# rtu01n02.net
KiCad netlist of a schematic drawn in EAGLE
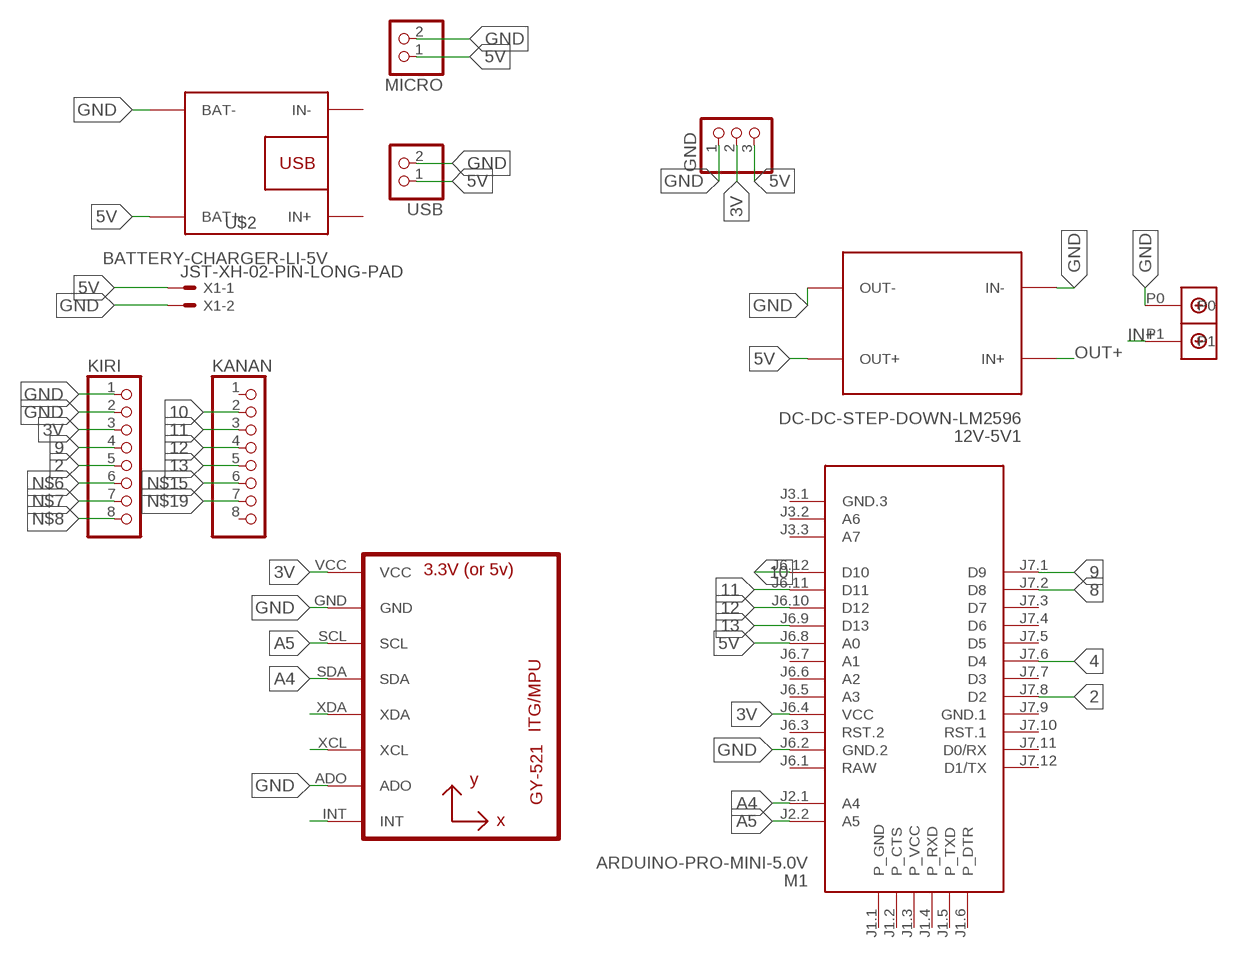
[diagram p0: schematic, sheet 1]

(export (version "E")
  (design (tool "Eeschema 10.0.6"))
  (components
    (comp (ref "12V-5V1")
      (value "DC-DC-STEP-DOWN-LM2596")
      (footprint "eagle-import:DC-DC-STEP-DOWN-LM2596")
      (libsource (lib "eagle-import") (part "DC-DC-STEP-DOWN-LM2596"))
    )
    (comp (ref "GND")
      (value "PINHD-1X3")
      (footprint "eagle-import:1X03")
      (libsource (lib "eagle-import") (part "PINHD-1X3"))
    )
    (comp (ref "KANAN")
      (value "PINHD-1X8")
      (footprint "eagle-import:1X08")
      (libsource (lib "eagle-import") (part "PINHD-1X8"))
    )
    (comp (ref "KIRI")
      (value "PINHD-1X8")
      (footprint "eagle-import:1X08")
      (libsource (lib "eagle-import") (part "PINHD-1X8"))
    )
    (comp (ref "M1")
      (value "ARDUINO-PRO-MINI-5.0V")
      (footprint "eagle-import:ARDUINO-PRO-MINI")
      (libsource (lib "eagle-import") (part "ARDUINO-PRO-MINI-5.0V"))
    )
    (comp (ref "MICRO")
      (value "PINHD-1X2")
      (footprint "eagle-import:1X02")
      (libsource (lib "eagle-import") (part "PINHD-1X2"))
    )
    (comp (ref "U$1")
      (value "DBCONN-1X2")
      (footprint "eagle-import:DBCONN-1X2")
      (libsource (lib "eagle-import") (part "DBCONN-1X2"))
    )
    (comp (ref "U$2")
      (value "BATTERY-CHARGER-LI-5V")
      (footprint "eagle-import:BATTERY-CHARGER-LI-5V")
      (libsource (lib "eagle-import") (part "BATTERY-CHARGER-LI-5V"))
    )
    (comp (ref "U1")
      (value "GY-521MPU6050")
      (footprint "eagle-import:GY-521")
      (libsource (lib "eagle-import") (part "GY-521MPU6050"))
    )
    (comp (ref "USB")
      (value "PINHD-1X2")
      (footprint "eagle-import:1X02")
      (libsource (lib "eagle-import") (part "PINHD-1X2"))
    )
    (comp (ref "X1")
      (value "JST-XH-02-PIN-LONG-PAD")
      (footprint "eagle-import:JST-XH-02-PACKAGE-LONG-PAD")
      (libsource (lib "eagle-import") (part "JST-XH-02-PIN-LONG-PAD"))
    )
  )
  (nets
    (net (code "1") (name "/GND.1") (class "Default")
      (node (ref "M1") (pin "J7.9") (pinfunction "GND.1_J7.9") (pintype "power_in"))
    )
    (net (code "2") (name "/IN+") (class "Default")
      (node (ref "U$1") (pin "P1") (pinfunction "P1_P1") (pintype "bidirectional"))
    )
    (net (code "3") (name "/OUT+") (class "Default")
      (node (ref "12V-5V1") (pin "IN+") (pinfunction "IN+_IN+") (pintype "bidirectional"))
    )
    (net (code "4") (name "/RAW") (class "Default")
      (node (ref "M1") (pin "J6.1") (pinfunction "RAW_J6.1") (pintype "power_in"))
    )
    (net (code "5") (name "2") (class "Default")
      (node (ref "KIRI") (pin "5") (pinfunction "5_5") (pintype "passive"))
      (node (ref "M1") (pin "J7.8") (pinfunction "D2_J7.8") (pintype "bidirectional"))
    )
    (net (code "6") (name "3V") (class "Default")
      (node (ref "GND") (pin "2") (pinfunction "2_2") (pintype "passive"))
      (node (ref "KIRI") (pin "3") (pinfunction "3_3") (pintype "passive"))
      (node (ref "M1") (pin "J6.4") (pinfunction "VCC_J6.4") (pintype "power_in"))
      (node (ref "U1") (pin "VCC") (pinfunction "VCC_VCC") (pintype "bidirectional"))
    )
    (net (code "7") (name "4") (class "Default")
      (node (ref "M1") (pin "J7.6") (pinfunction "D4_J7.6") (pintype "bidirectional"))
    )
    (net (code "8") (name "5V") (class "Default")
      (node (ref "12V-5V1") (pin "OUT+") (pinfunction "OUT+_OUT+") (pintype "bidirectional"))
      (node (ref "GND") (pin "3") (pinfunction "3_3") (pintype "passive"))
      (node (ref "M1") (pin "J6.8") (pinfunction "A0_J6.8") (pintype "bidirectional"))
      (node (ref "MICRO") (pin "1") (pinfunction "1_1") (pintype "passive"))
      (node (ref "U$2") (pin "BAT+") (pinfunction "BAT+_BAT+") (pintype "bidirectional"))
      (node (ref "USB") (pin "1") (pinfunction "1_1") (pintype "passive"))
      (node (ref "X1") (pin "1") (pinfunction "S_1") (pintype "passive"))
    )
    (net (code "9") (name "8") (class "Default")
      (node (ref "M1") (pin "J7.2") (pinfunction "D8_J7.2") (pintype "bidirectional"))
    )
    (net (code "10") (name "9") (class "Default")
      (node (ref "KIRI") (pin "4") (pinfunction "4_4") (pintype "passive"))
      (node (ref "M1") (pin "J7.1") (pinfunction "D9_J7.1") (pintype "bidirectional"))
    )
    (net (code "11") (name "10") (class "Default")
      (node (ref "KANAN") (pin "2") (pinfunction "2_2") (pintype "passive"))
      (node (ref "M1") (pin "J6.12") (pinfunction "D10_J6.12") (pintype "bidirectional"))
    )
    (net (code "12") (name "11") (class "Default")
      (node (ref "KANAN") (pin "3") (pinfunction "3_3") (pintype "passive"))
      (node (ref "M1") (pin "J6.11") (pinfunction "D11_J6.11") (pintype "bidirectional"))
    )
    (net (code "13") (name "12") (class "Default")
      (node (ref "KANAN") (pin "4") (pinfunction "4_4") (pintype "passive"))
      (node (ref "M1") (pin "J6.10") (pinfunction "D12_J6.10") (pintype "bidirectional"))
    )
    (net (code "14") (name "13") (class "Default")
      (node (ref "KANAN") (pin "5") (pinfunction "5_5") (pintype "passive"))
      (node (ref "M1") (pin "J6.9") (pinfunction "D13_J6.9") (pintype "bidirectional"))
    )
    (net (code "15") (name "A4") (class "Default")
      (node (ref "M1") (pin "J2.1") (pinfunction "A4_J2.1") (pintype "bidirectional"))
      (node (ref "U1") (pin "SDA") (pinfunction "SDA_SDA") (pintype "bidirectional"))
    )
    (net (code "16") (name "A5") (class "Default")
      (node (ref "M1") (pin "J2.2") (pinfunction "A5_J2.2") (pintype "bidirectional"))
      (node (ref "U1") (pin "SCL") (pinfunction "SCL_SCL") (pintype "bidirectional"))
    )
    (net (code "17") (name "GND") (class "Default")
      (node (ref "12V-5V1") (pin "IN-") (pinfunction "IN-_IN-") (pintype "bidirectional"))
      (node (ref "12V-5V1") (pin "OUT-") (pinfunction "OUT-_OUT-") (pintype "bidirectional"))
      (node (ref "GND") (pin "1") (pinfunction "1_1") (pintype "passive"))
      (node (ref "KIRI") (pin "1") (pinfunction "1_1") (pintype "passive"))
      (node (ref "KIRI") (pin "2") (pinfunction "2_2") (pintype "passive"))
      (node (ref "M1") (pin "J6.2") (pinfunction "GND.2_J6.2") (pintype "power_in"))
      (node (ref "MICRO") (pin "2") (pinfunction "2_2") (pintype "passive"))
      (node (ref "U$1") (pin "P0") (pinfunction "P0_P0") (pintype "bidirectional"))
      (node (ref "U$2") (pin "BAT-") (pinfunction "BAT-_BAT-") (pintype "bidirectional"))
      (node (ref "U1") (pin "ADO") (pinfunction "ADO_ADO") (pintype "bidirectional"))
      (node (ref "U1") (pin "GND") (pinfunction "GND_GND") (pintype "bidirectional"))
      (node (ref "USB") (pin "2") (pinfunction "2_2") (pintype "passive"))
      (node (ref "X1") (pin "2") (pinfunction "S_2") (pintype "passive"))
    )
    (net (code "18") (name "N$6") (class "Default")
      (node (ref "KIRI") (pin "6") (pinfunction "6_6") (pintype "passive"))
    )
    (net (code "19") (name "N$7") (class "Default")
      (node (ref "KIRI") (pin "7") (pinfunction "7_7") (pintype "passive"))
    )
    (net (code "20") (name "N$8") (class "Default")
      (node (ref "KIRI") (pin "8") (pinfunction "8_8") (pintype "passive"))
    )
    (net (code "21") (name "N$15") (class "Default")
      (node (ref "KANAN") (pin "6") (pinfunction "6_6") (pintype "passive"))
    )
    (net (code "22") (name "N$19") (class "Default")
      (node (ref "KANAN") (pin "7") (pinfunction "7_7") (pintype "passive"))
    )
    (net (code "23") (name "unconnected-(KANAN-Pad1)") (class "Default")
      (node (ref "KANAN") (pin "1") (pinfunction "1_1") (pintype "passive"))
    )
    (net (code "24") (name "unconnected-(KANAN-Pad8)") (class "Default")
      (node (ref "KANAN") (pin "8") (pinfunction "8_8") (pintype "passive"))
    )
    (net (code "25") (name "unconnected-(M1-A1-PadJ6.7)") (class "Default")
      (node (ref "M1") (pin "J6.7") (pinfunction "A1_J6.7") (pintype "bidirectional"))
    )
    (net (code "26") (name "unconnected-(M1-A2-PadJ6.6)") (class "Default")
      (node (ref "M1") (pin "J6.6") (pinfunction "A2_J6.6") (pintype "bidirectional"))
    )
    (net (code "27") (name "unconnected-(M1-A3-PadJ6.5)") (class "Default")
      (node (ref "M1") (pin "J6.5") (pinfunction "A3_J6.5") (pintype "bidirectional"))
    )
    (net (code "28") (name "unconnected-(M1-A6-PadJ3.2)") (class "Default")
      (node (ref "M1") (pin "J3.2") (pinfunction "A6_J3.2") (pintype "bidirectional"))
    )
    (net (code "29") (name "unconnected-(M1-A7-PadJ3.3)") (class "Default")
      (node (ref "M1") (pin "J3.3") (pinfunction "A7_J3.3") (pintype "bidirectional"))
    )
    (net (code "30") (name "unconnected-(M1-D0{slash}RX-PadJ7.11)") (class "Default")
      (node (ref "M1") (pin "J7.11") (pinfunction "D0/RX_J7.11") (pintype "bidirectional"))
    )
    (net (code "31") (name "unconnected-(M1-D1{slash}TX-PadJ7.12)") (class "Default")
      (node (ref "M1") (pin "J7.12") (pinfunction "D1/TX_J7.12") (pintype "bidirectional"))
    )
    (net (code "32") (name "unconnected-(M1-D3-PadJ7.7)") (class "Default")
      (node (ref "M1") (pin "J7.7") (pinfunction "D3_J7.7") (pintype "bidirectional"))
    )
    (net (code "33") (name "unconnected-(M1-D5-PadJ7.5)") (class "Default")
      (node (ref "M1") (pin "J7.5") (pinfunction "D5_J7.5") (pintype "bidirectional"))
    )
    (net (code "34") (name "unconnected-(M1-D6-PadJ7.4)") (class "Default")
      (node (ref "M1") (pin "J7.4") (pinfunction "D6_J7.4") (pintype "bidirectional"))
    )
    (net (code "35") (name "unconnected-(M1-D7-PadJ7.3)") (class "Default")
      (node (ref "M1") (pin "J7.3") (pinfunction "D7_J7.3") (pintype "bidirectional"))
    )
    (net (code "36") (name "unconnected-(M1-GND.3-PadJ3.1)") (class "Default")
      (node (ref "M1") (pin "J3.1") (pinfunction "GND.3_J3.1") (pintype "bidirectional"))
    )
    (net (code "37") (name "unconnected-(M1-P_CTS-PadJ1.2)") (class "Default")
      (node (ref "M1") (pin "J1.2") (pinfunction "P_CTS_J1.2") (pintype "bidirectional"))
    )
    (net (code "38") (name "unconnected-(M1-P_DTR-PadJ1.6)") (class "Default")
      (node (ref "M1") (pin "J1.6") (pinfunction "P_DTR_J1.6") (pintype "bidirectional"))
    )
    (net (code "39") (name "unconnected-(M1-P_GND-PadJ1.1)") (class "Default")
      (node (ref "M1") (pin "J1.1") (pinfunction "P_GND_J1.1") (pintype "bidirectional"))
    )
    (net (code "40") (name "unconnected-(M1-P_RXD-PadJ1.4)") (class "Default")
      (node (ref "M1") (pin "J1.4") (pinfunction "P_RXD_J1.4") (pintype "bidirectional"))
    )
    (net (code "41") (name "unconnected-(M1-P_TXD-PadJ1.5)") (class "Default")
      (node (ref "M1") (pin "J1.5") (pinfunction "P_TXD_J1.5") (pintype "bidirectional"))
    )
    (net (code "42") (name "unconnected-(M1-P_VCC-PadJ1.3)") (class "Default")
      (node (ref "M1") (pin "J1.3") (pinfunction "P_VCC_J1.3") (pintype "bidirectional"))
    )
    (net (code "43") (name "unconnected-(M1-RST.1-PadJ7.10)") (class "Default")
      (node (ref "M1") (pin "J7.10") (pinfunction "RST.1_J7.10") (pintype "bidirectional"))
    )
    (net (code "44") (name "unconnected-(M1-RST.2-PadJ6.3)") (class "Default")
      (node (ref "M1") (pin "J6.3") (pinfunction "RST.2_J6.3") (pintype "bidirectional"))
    )
    (net (code "45") (name "unconnected-(U$2-PadIN+)") (class "Default")
      (node (ref "U$2") (pin "IN+") (pinfunction "IN+_IN+") (pintype "bidirectional"))
    )
    (net (code "46") (name "unconnected-(U$2-PadIN-)") (class "Default")
      (node (ref "U$2") (pin "IN-") (pinfunction "IN-_IN-") (pintype "bidirectional"))
    )
    (net (code "47") (name "unconnected-(U1-PadINT)") (class "Default")
      (node (ref "U1") (pin "INT") (pinfunction "INT_INT") (pintype "bidirectional"))
    )
    (net (code "48") (name "unconnected-(U1-PadXCL)") (class "Default")
      (node (ref "U1") (pin "XCL") (pinfunction "XCL_XCL") (pintype "bidirectional"))
    )
    (net (code "49") (name "unconnected-(U1-PadXDA)") (class "Default")
      (node (ref "U1") (pin "XDA") (pinfunction "XDA_XDA") (pintype "bidirectional"))
    )
  )
)
